# RFID_revb.net
KiCad netlist of a schematic drawn in EAGLE
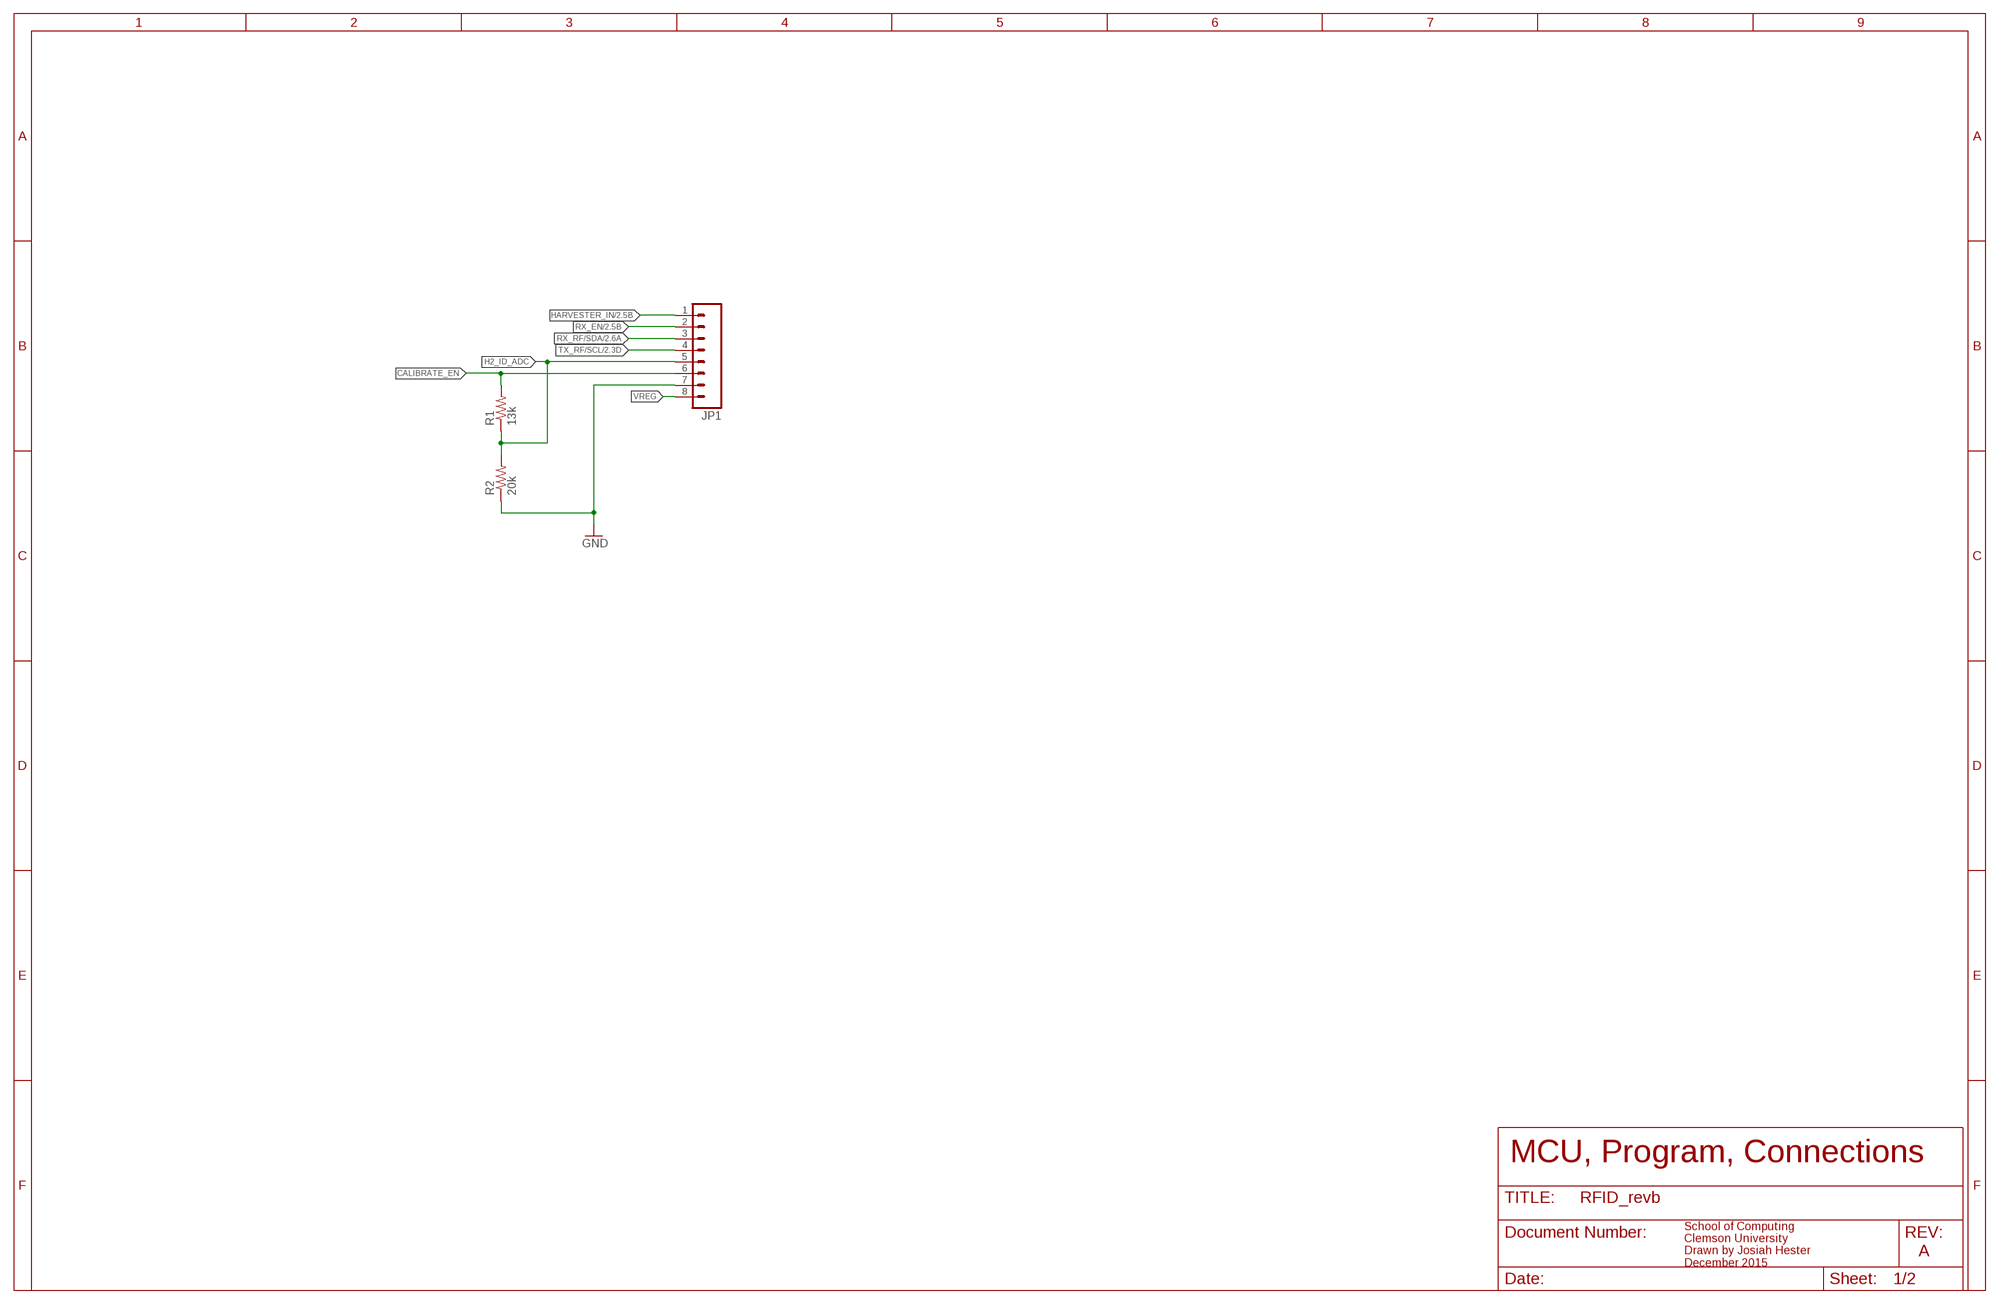
[diagram p0: schematic, sheet 1]
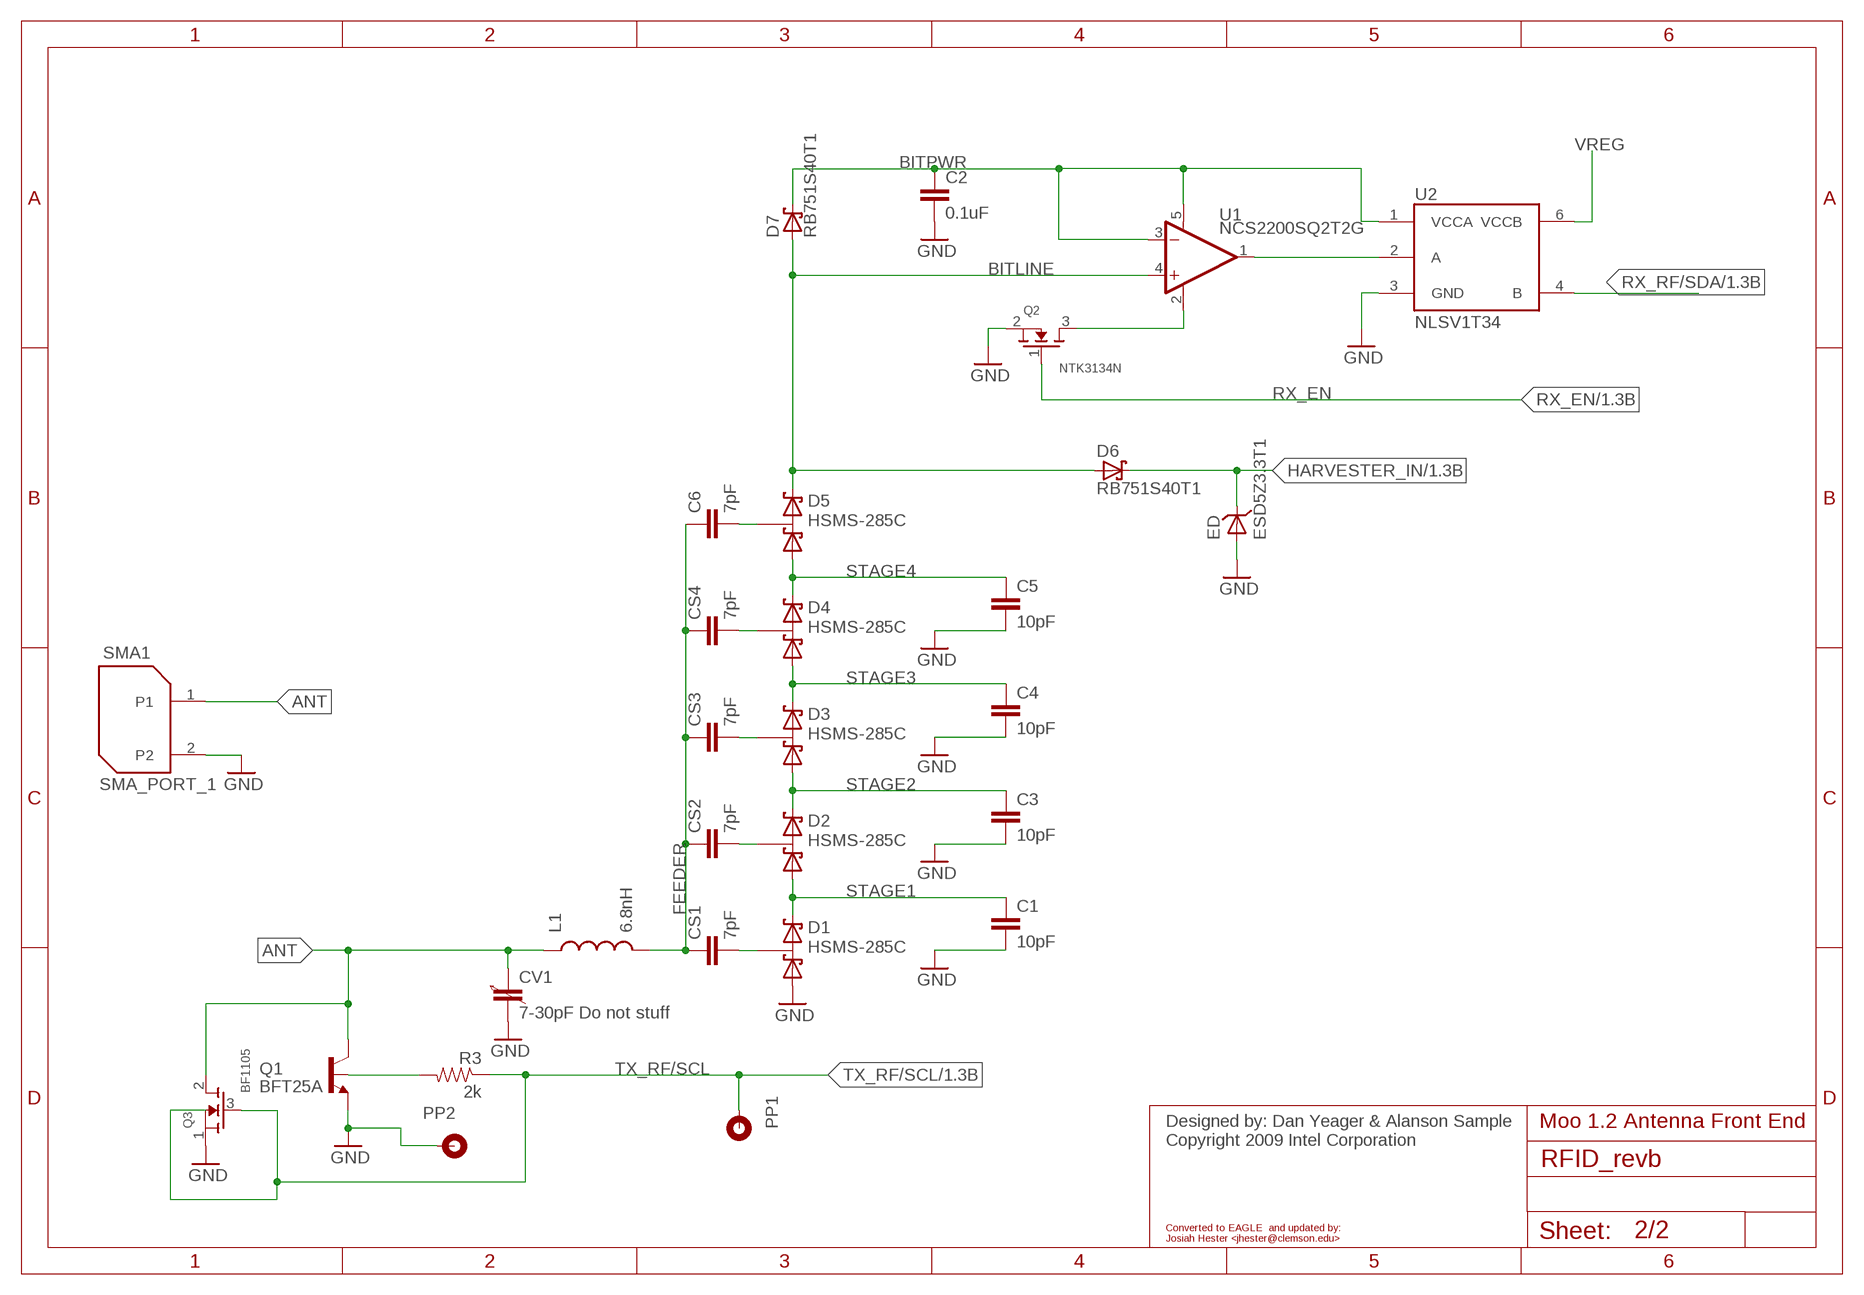
[diagram p1: schematic, sheet 2]

(export (version "E")
  (design (tool "Eeschema 10.0.6"))
  (components
    (comp (ref "C1")
      (value "10pF")
      (footprint "eagle-import:0402")
      (fields (field (name "MPN") "GRM1555C1H100JA01D "))
      (libsource (lib "eagle-import") (part "C-EU"))
    )
    (comp (ref "C2")
      (value "0.1uF")
      (footprint "eagle-import:0402")
      (fields (field (name "MPN") "0402YD104KAT2A"))
      (libsource (lib "eagle-import") (part "C-EU"))
    )
    (comp (ref "C3")
      (value "10pF")
      (footprint "eagle-import:0402")
      (fields (field (name "MPN") "GRM1555C1H100JA01D "))
      (libsource (lib "eagle-import") (part "C-EU"))
    )
    (comp (ref "C4")
      (value "10pF")
      (footprint "eagle-import:0402")
      (fields (field (name "MPN") "GRM1555C1H100JA01D "))
      (libsource (lib "eagle-import") (part "C-EU"))
    )
    (comp (ref "C5")
      (value "10pF")
      (footprint "eagle-import:0402")
      (fields (field (name "MPN") "GRM1555C1H100JA01D "))
      (libsource (lib "eagle-import") (part "C-EU"))
    )
    (comp (ref "C6")
      (value "7pF")
      (footprint "eagle-import:0402")
      (fields (field (name "MPN") "GRM1555C1H7R0DA01D"))
      (libsource (lib "eagle-import") (part "C-EU"))
    )
    (comp (ref "CS1")
      (value "7pF")
      (footprint "eagle-import:0402")
      (fields (field (name "MPN") "GRM1555C1H7R0DA01D "))
      (libsource (lib "eagle-import") (part "C-EU"))
    )
    (comp (ref "CS2")
      (value "7pF")
      (footprint "eagle-import:0402")
      (fields (field (name "MPN") "GRM1555C1H7R0DA01D "))
      (libsource (lib "eagle-import") (part "C-EU"))
    )
    (comp (ref "CS3")
      (value "7pF")
      (footprint "eagle-import:0402")
      (fields (field (name "MPN") "GRM1555C1H7R0DA01D "))
      (libsource (lib "eagle-import") (part "C-EU"))
    )
    (comp (ref "CS4")
      (value "7pF")
      (footprint "eagle-import:0402")
      (fields (field (name "MPN") "GRM1555C1H7R0DA01D"))
      (libsource (lib "eagle-import") (part "C-EU"))
    )
    (comp (ref "CV1")
      (value "7-30pF Do not stuff")
      (footprint "eagle-import:VAR-CAP_603_1PRIMARY")
      (fields (field (name "MPN") "TZY2R250AC01R00 "))
      (libsource (lib "eagle-import") (part "VAR-CAP_603_1"))
    )
    (comp (ref "D1")
      (value "HSMS-285C")
      (footprint "eagle-import:SOT-323,_HSMS-285C_1PRIMARY")
      (fields (field (name "MPN") "HSMS-285C-BLKG"))
      (libsource (lib "eagle-import") (part "HSMS-285C"))
    )
    (comp (ref "D2")
      (value "HSMS-285C")
      (footprint "eagle-import:SOT-323,_HSMS-285C_1PRIMARY")
      (fields (field (name "MPN") "HSMS-285C-BLKG"))
      (libsource (lib "eagle-import") (part "HSMS-285C"))
    )
    (comp (ref "D3")
      (value "HSMS-285C")
      (footprint "eagle-import:SOT-323,_HSMS-285C_1PRIMARY")
      (fields (field (name "MPN") "HSMS-285C-BLKG"))
      (libsource (lib "eagle-import") (part "HSMS-285C"))
    )
    (comp (ref "D4")
      (value "HSMS-285C")
      (footprint "eagle-import:SOT-323,_HSMS-285C_1PRIMARY")
      (fields (field (name "MPN") "HSMS-285C-BLKG"))
      (libsource (lib "eagle-import") (part "HSMS-285C"))
    )
    (comp (ref "D5")
      (value "HSMS-285C")
      (footprint "eagle-import:SOT-323,_HSMS-285C_1PRIMARY")
      (fields (field (name "MPN") "HSMS-285C-BLKG"))
      (libsource (lib "eagle-import") (part "HSMS-285C"))
    )
    (comp (ref "D6")
      (value "RB751S40T1")
      (footprint "eagle-import:SOD-523_1PRIMARY")
      (fields (field (name "MPN") "RB751S40T1G"))
      (libsource (lib "eagle-import") (part "RB751S40T1"))
    )
    (comp (ref "D7")
      (value "RB751S40T1")
      (footprint "eagle-import:SOD-523_1PRIMARY")
      (fields (field (name "MPN") "RB751S40T1G"))
      (libsource (lib "eagle-import") (part "RB751S40T1"))
    )
    (comp (ref "ED")
      (value "ESD5Z3.3T1")
      (footprint "eagle-import:SOD-523_1PRIMARY")
      (fields (field (name "MPN") "ESD5Z3.3T1G"))
      (libsource (lib "eagle-import") (part "ESD5Z3.3T1"))
    )
    (comp (ref "L1")
      (value "6.8nH")
      (footprint "eagle-import:0603_1PRIMARY")
      (fields (field (name "MPN") "MLG1608B6N8DT000 "))
      (libsource (lib "eagle-import") (part "0603_1"))
    )
    (comp (ref "PP1")
      (value "PROBE_POINT_2")
      (footprint "eagle-import:PROBE_POINT_2PRIMARY")
      (libsource (lib "eagle-import") (part "PROBE_POINT_2"))
    )
    (comp (ref "PP2")
      (value "PROBE_POINT_1")
      (footprint "eagle-import:PROBE_POINT_2PRIMARY")
      (libsource (lib "eagle-import") (part "PROBE_POINT_1"))
    )
    (comp (ref "Q1")
      (value "BFT25A")
      (footprint "eagle-import:SOT-23_1PRIMARY")
      (fields (field (name "MPN") "BFT25A,215 "))
      (libsource (lib "eagle-import") (part "BFT25A"))
    )
    (comp (ref "Q2")
      (value "NTK3134N")
      (footprint "eagle-import:SOT723_1PRIMARY")
      (fields (field (name "MPN") "NTK3134NT1G"))
      (libsource (lib "eagle-import") (part "NTK3134N"))
    )
    (comp (ref "Q3")
      (value "BF1105")
      (footprint "eagle-import:SOT-143R")
      (fields (field (name "MPN") "BF1105R,215 "))
      (libsource (lib "eagle-import") (part "BF1105"))
    )
    (comp (ref "R3")
      (value "2k")
      (footprint "eagle-import:0402")
      (fields (field (name "MPN") "CRCW04022K00FKED"))
      (libsource (lib "eagle-import") (part "R-EU"))
    )
    (comp (ref "SMA1")
      (value "SMA_PORT_1")
      (footprint "eagle-import:SMA_PORT_1PRIMARY")
      (libsource (lib "eagle-import") (part "SMA_PORT_1"))
    )
    (comp (ref "U1")
      (value "NCS2200SQ2T2G")
      (footprint "eagle-import:SC70-5_1PRIMARY")
      (fields (field (name "MPN") "NCS2200SQ2T2G "))
      (libsource (lib "eagle-import") (part "NCS2200SQ2T2G"))
    )
    (comp (ref "U2")
      (value "NLSV1T34")
      (footprint "eagle-import:ULLGA6")
      (fields (field (name "MPN") "NLSV1T34AMX1TCG "))
      (libsource (lib "eagle-import") (part "NLSV1T34"))
    )
    (comp (ref "JP1")
      (value "M081.27MM")
      (footprint "eagle-import:1X08-1.27MM")
      (fields (field (name "MPN") "GRPB081VWVN-RC "))
      (libsource (lib "eagle-import") (part "M081.27MM"))
    )
    (comp (ref "R1")
      (value "13k")
      (footprint "eagle-import:0603")
      (fields (field (name "MPN") "RC0603FR-0713KL"))
      (libsource (lib "eagle-import") (part "R-EU0603"))
    )
    (comp (ref "R2")
      (value "20k")
      (footprint "eagle-import:0603")
      (fields (field (name "MPN") "CRCW060320K0FKEA"))
      (libsource (lib "eagle-import") (part "R-EU0603"))
    )
  )
  (nets
    (net (code "1") (name "ANT") (class "Default")
      (node (ref "CV1") (pin "1") (pinfunction "1_1") (pintype "passive"))
      (node (ref "L1") (pin "1") (pinfunction "1_1") (pintype "passive"))
      (node (ref "Q1") (pin "3") (pinfunction "C_3") (pintype "passive"))
      (node (ref "Q3") (pin "2") (pinfunction "D_2") (pintype "bidirectional"))
      (node (ref "SMA1") (pin "1") (pinfunction "P1_1") (pintype "bidirectional"))
    )
    (net (code "2") (name "BITLINE") (class "Default")
      (node (ref "D5") (pin "2") (pinfunction "2_2") (pintype "passive"))
      (node (ref "D6") (pin "2") (pinfunction "A_2") (pintype "passive"))
      (node (ref "D7") (pin "2") (pinfunction "A_2") (pintype "passive"))
      (node (ref "U1") (pin "4") (pinfunction "4_4") (pintype "input"))
    )
    (net (code "3") (name "BITPWR") (class "Default")
      (node (ref "C2") (pin "1") (pinfunction "1_1") (pintype "passive"))
      (node (ref "D7") (pin "1") (pinfunction "C_1") (pintype "passive"))
      (node (ref "U1") (pin "3") (pinfunction "3_3") (pintype "input"))
      (node (ref "U1") (pin "5") (pinfunction "5_5") (pintype "input"))
      (node (ref "U2") (pin "1") (pinfunction "VCCA_1") (pintype "bidirectional"))
    )
    (net (code "4") (name "CALIBRATE_EN") (class "Default")
      (node (ref "JP1") (pin "6") (pinfunction "6_6") (pintype "passive"))
      (node (ref "R1") (pin "2") (pinfunction "2_2") (pintype "passive"))
    )
    (net (code "5") (name "FEEDER") (class "Default")
      (node (ref "C6") (pin "1") (pinfunction "1_1") (pintype "passive"))
      (node (ref "CS1") (pin "1") (pinfunction "1_1") (pintype "passive"))
      (node (ref "CS2") (pin "1") (pinfunction "1_1") (pintype "passive"))
      (node (ref "CS3") (pin "1") (pinfunction "1_1") (pintype "passive"))
      (node (ref "CS4") (pin "1") (pinfunction "1_1") (pintype "passive"))
      (node (ref "L1") (pin "2") (pinfunction "2_2") (pintype "passive"))
    )
    (net (code "6") (name "GND") (class "Default")
      (node (ref "C1") (pin "2") (pinfunction "2_2") (pintype "passive"))
      (node (ref "C2") (pin "2") (pinfunction "2_2") (pintype "passive"))
      (node (ref "C3") (pin "2") (pinfunction "2_2") (pintype "passive"))
      (node (ref "C4") (pin "2") (pinfunction "2_2") (pintype "passive"))
      (node (ref "C5") (pin "2") (pinfunction "2_2") (pintype "passive"))
      (node (ref "CV1") (pin "2") (pinfunction "2_2") (pintype "passive"))
      (node (ref "D1") (pin "1") (pinfunction "1_1") (pintype "passive"))
      (node (ref "ED") (pin "2") (pinfunction "2_2") (pintype "passive"))
      (node (ref "JP1") (pin "7") (pinfunction "7_7") (pintype "passive"))
      (node (ref "PP2") (pin "1") (pinfunction "1_1") (pintype "bidirectional"))
      (node (ref "Q1") (pin "2") (pinfunction "E_2") (pintype "passive"))
      (node (ref "Q2") (pin "2") (pinfunction "2_2") (pintype "bidirectional"))
      (node (ref "Q3") (pin "1") (pinfunction "S_1") (pintype "bidirectional"))
      (node (ref "R2") (pin "1") (pinfunction "1_1") (pintype "passive"))
      (node (ref "SMA1") (pin "2") (pinfunction "P2_2") (pintype "bidirectional"))
      (node (ref "U2") (pin "3") (pinfunction "GND_3") (pintype "bidirectional"))
    )
    (net (code "7") (name "H2_ID_ADC") (class "Default")
      (node (ref "JP1") (pin "5") (pinfunction "5_5") (pintype "passive"))
      (node (ref "R1") (pin "1") (pinfunction "1_1") (pintype "passive"))
      (node (ref "R2") (pin "2") (pinfunction "2_2") (pintype "passive"))
    )
    (net (code "8") (name "HARVESTER_IN") (class "Default")
      (node (ref "D6") (pin "1") (pinfunction "C_1") (pintype "passive"))
      (node (ref "ED") (pin "1") (pinfunction "1_1") (pintype "passive"))
      (node (ref "JP1") (pin "1") (pinfunction "1_1") (pintype "passive"))
    )
    (net (code "9") (name "Net-(C6-Pad2)") (class "Default")
      (node (ref "C6") (pin "2") (pinfunction "2_2") (pintype "passive"))
      (node (ref "D5") (pin "3") (pinfunction "3_3") (pintype "passive"))
    )
    (net (code "10") (name "Net-(CS1-Pad2)") (class "Default")
      (node (ref "CS1") (pin "2") (pinfunction "2_2") (pintype "passive"))
      (node (ref "D1") (pin "3") (pinfunction "3_3") (pintype "passive"))
    )
    (net (code "11") (name "Net-(CS2-Pad2)") (class "Default")
      (node (ref "CS2") (pin "2") (pinfunction "2_2") (pintype "passive"))
      (node (ref "D2") (pin "3") (pinfunction "3_3") (pintype "passive"))
    )
    (net (code "12") (name "Net-(CS3-Pad2)") (class "Default")
      (node (ref "CS3") (pin "2") (pinfunction "2_2") (pintype "passive"))
      (node (ref "D3") (pin "3") (pinfunction "3_3") (pintype "passive"))
    )
    (net (code "13") (name "Net-(CS4-Pad2)") (class "Default")
      (node (ref "CS4") (pin "2") (pinfunction "2_2") (pintype "passive"))
      (node (ref "D4") (pin "3") (pinfunction "3_3") (pintype "passive"))
    )
    (net (code "14") (name "Net-(Q1-B)") (class "Default")
      (node (ref "Q1") (pin "1") (pinfunction "B_1") (pintype "passive"))
      (node (ref "R3") (pin "2") (pinfunction "2_2") (pintype "passive"))
    )
    (net (code "15") (name "Net-(Q2-Pad3)") (class "Default")
      (node (ref "Q2") (pin "3") (pinfunction "3_3") (pintype "bidirectional"))
      (node (ref "U1") (pin "2") (pinfunction "2_2") (pintype "input"))
    )
    (net (code "16") (name "Net-(U2-A)") (class "Default")
      (node (ref "U1") (pin "1") (pinfunction "1_1") (pintype "output"))
      (node (ref "U2") (pin "2") (pinfunction "A_2") (pintype "bidirectional"))
    )
    (net (code "17") (name "RX_EN") (class "Default")
      (node (ref "JP1") (pin "2") (pinfunction "2_2") (pintype "passive"))
      (node (ref "Q2") (pin "1") (pinfunction "1_1") (pintype "bidirectional"))
    )
    (net (code "18") (name "RX_RF{slash}SDA") (class "Default")
      (node (ref "JP1") (pin "3") (pinfunction "3_3") (pintype "passive"))
      (node (ref "U2") (pin "4") (pinfunction "B_4") (pintype "bidirectional"))
    )
    (net (code "19") (name "STAGE1") (class "Default")
      (node (ref "C1") (pin "1") (pinfunction "1_1") (pintype "passive"))
      (node (ref "D1") (pin "2") (pinfunction "2_2") (pintype "passive"))
      (node (ref "D2") (pin "1") (pinfunction "1_1") (pintype "passive"))
    )
    (net (code "20") (name "STAGE2") (class "Default")
      (node (ref "C3") (pin "1") (pinfunction "1_1") (pintype "passive"))
      (node (ref "D2") (pin "2") (pinfunction "2_2") (pintype "passive"))
      (node (ref "D3") (pin "1") (pinfunction "1_1") (pintype "passive"))
    )
    (net (code "21") (name "STAGE3") (class "Default")
      (node (ref "C4") (pin "1") (pinfunction "1_1") (pintype "passive"))
      (node (ref "D3") (pin "2") (pinfunction "2_2") (pintype "passive"))
      (node (ref "D4") (pin "1") (pinfunction "1_1") (pintype "passive"))
    )
    (net (code "22") (name "STAGE4") (class "Default")
      (node (ref "C5") (pin "1") (pinfunction "1_1") (pintype "passive"))
      (node (ref "D4") (pin "2") (pinfunction "2_2") (pintype "passive"))
      (node (ref "D5") (pin "1") (pinfunction "1_1") (pintype "passive"))
    )
    (net (code "23") (name "TX_RF{slash}SCL") (class "Default")
      (node (ref "JP1") (pin "4") (pinfunction "4_4") (pintype "passive"))
      (node (ref "PP1") (pin "1") (pinfunction "1_1") (pintype "bidirectional"))
      (node (ref "Q3") (pin "3") (pinfunction "G_3") (pintype "bidirectional"))
      (node (ref "Q3") (pin "4") (pinfunction "G2_4") (pintype "bidirectional"))
      (node (ref "R3") (pin "1") (pinfunction "1_1") (pintype "passive"))
    )
    (net (code "24") (name "VREG") (class "Default")
      (node (ref "JP1") (pin "8") (pinfunction "8_8") (pintype "passive"))
      (node (ref "U2") (pin "6") (pinfunction "VCCB_6") (pintype "bidirectional"))
    )
  )
)
